# ProProject_J-Link_OB-RA4M2_20230930_V1_0.net
KiCad netlist of a schematic drawn in EasyEDA Pro
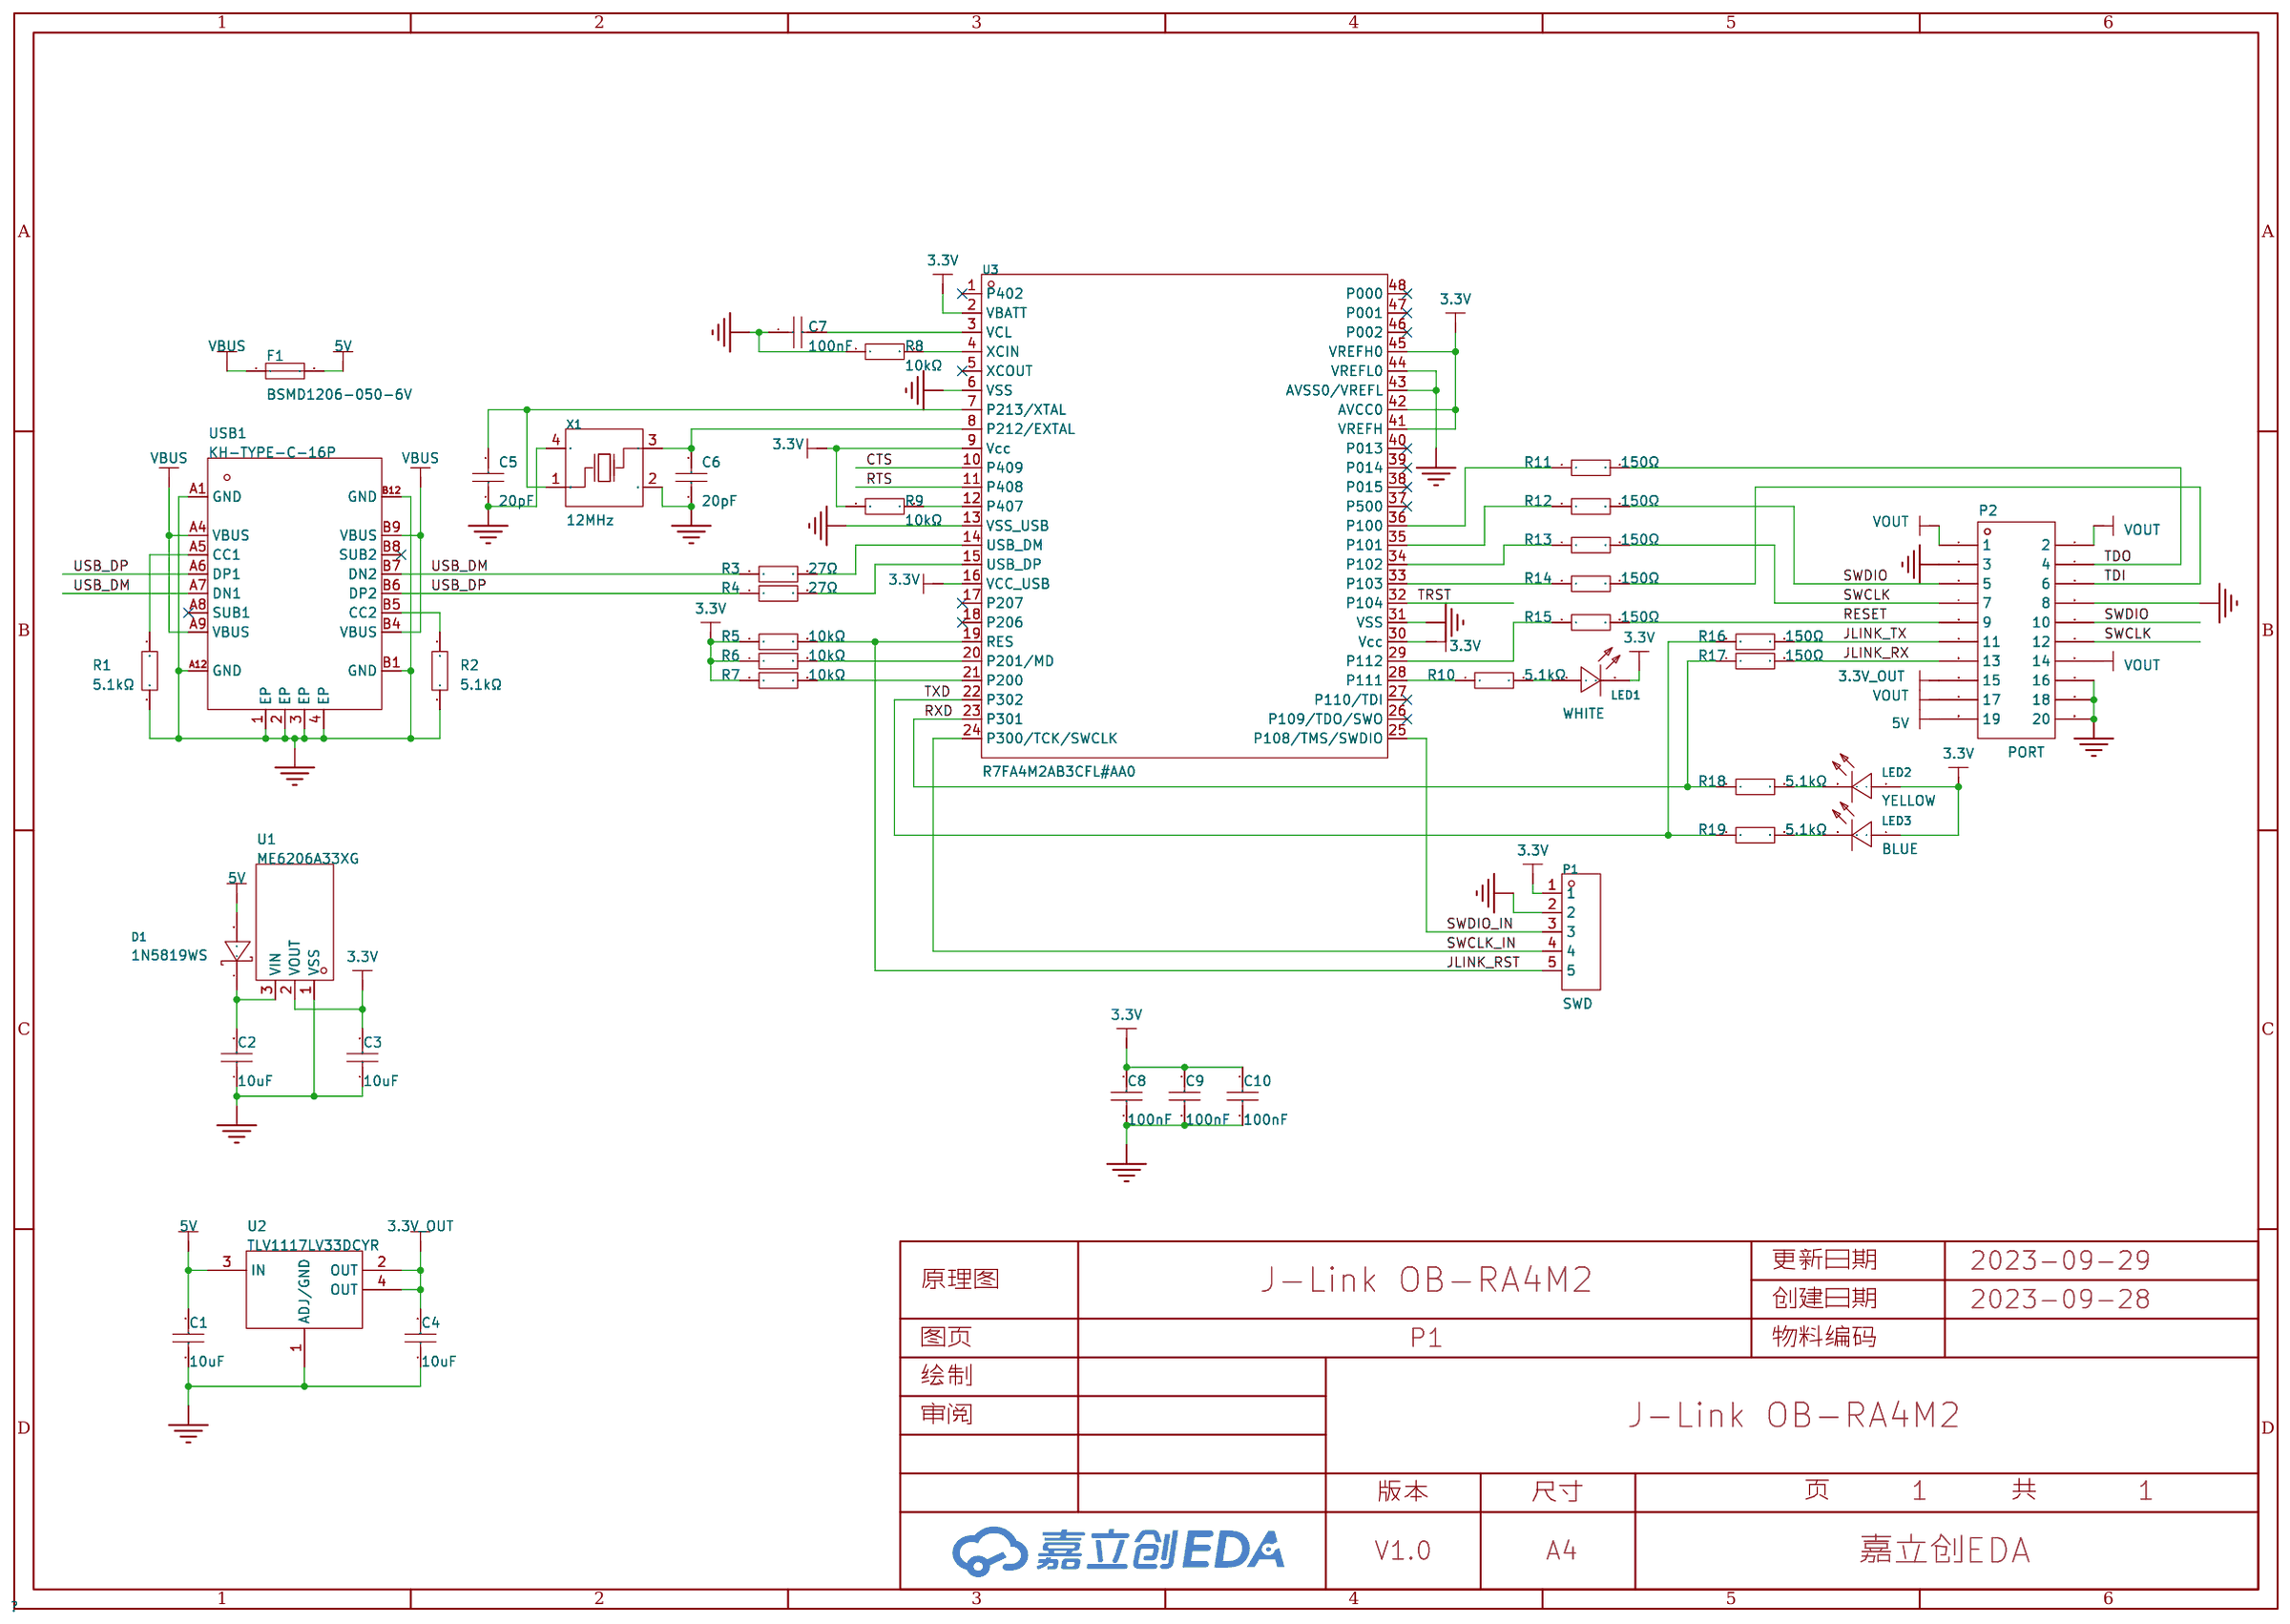
[diagram p0: schematic sheet]

(export (version "E")
  (design (tool "Eeschema 10.0.6"))
  (components
    (comp (ref "C1")
      (value "10uF")
      (footprint "easyedapro:C0805")
      (description "容值:10uF;精度:±10%;额定电压:25V;材质(温度系数):X5R;")
      (fields
        (field (name "Manufacturer Part") "CL21A106KAYNNNE")
        (field (name "Manufacturer") "SAMSUNG(三星)")
      )
      (libsource (lib "easyedapro") (part "CL21A106KAYNNNE"))
    )
    (comp (ref "C2")
      (value "10uF")
      (footprint "easyedapro:C0805")
      (description "容值:10uF;精度:±10%;额定电压:25V;材质(温度系数):X5R;")
      (fields
        (field (name "Manufacturer Part") "CL21A106KAYNNNE")
        (field (name "Manufacturer") "SAMSUNG(三星)")
      )
      (libsource (lib "easyedapro") (part "CL21A106KAYNNNE"))
    )
    (comp (ref "C3")
      (value "10uF")
      (footprint "easyedapro:C0805")
      (description "容值:10uF;精度:±10%;额定电压:25V;材质(温度系数):X5R;")
      (fields
        (field (name "Manufacturer Part") "CL21A106KAYNNNE")
        (field (name "Manufacturer") "SAMSUNG(三星)")
      )
      (libsource (lib "easyedapro") (part "CL21A106KAYNNNE"))
    )
    (comp (ref "C4")
      (value "10uF")
      (footprint "easyedapro:C0805")
      (description "容值:10uF;精度:±10%;额定电压:25V;材质(温度系数):X5R;")
      (fields
        (field (name "Manufacturer Part") "CL21A106KAYNNNE")
        (field (name "Manufacturer") "SAMSUNG(三星)")
      )
      (libsource (lib "easyedapro") (part "CL21A106KAYNNNE"))
    )
    (comp (ref "C5")
      (value "20pF")
      (footprint "easyedapro:C0805")
      (description "容值:20pF;精度:±5%;额定电压:50V;材质(温度系数):C0G;")
      (fields
        (field (name "Manufacturer Part") "CL10C200JB8NNNC")
        (field (name "Manufacturer") "SAMSUNG(三星)")
      )
      (libsource (lib "easyedapro") (part "CL21C200JBANNNC"))
    )
    (comp (ref "C6")
      (value "20pF")
      (footprint "easyedapro:C0805")
      (description "容值:20pF;精度:±5%;额定电压:50V;材质(温度系数):C0G;")
      (fields
        (field (name "Manufacturer Part") "CL10C200JB8NNNC")
        (field (name "Manufacturer") "SAMSUNG(三星)")
      )
      (libsource (lib "easyedapro") (part "CL21C200JBANNNC"))
    )
    (comp (ref "C7")
      (value "100nF")
      (footprint "easyedapro:C0805")
      (description "容值:100nF;精度:±10%;额定电压:50V;材质(温度系数):X7R;")
      (fields (field (name "Manufacturer Part") "0603B104K500NT") (field (name "Manufacturer") "FH(风华)"))
      (libsource (lib "easyedapro") (part "CC0805KRX7R9BB104"))
    )
    (comp (ref "C8")
      (value "100nF")
      (footprint "easyedapro:C0805")
      (description "容值:100nF;精度:±10%;额定电压:50V;材质(温度系数):X7R;")
      (fields (field (name "Manufacturer Part") "0603B104K500NT") (field (name "Manufacturer") "FH(风华)"))
      (libsource (lib "easyedapro") (part "CC0805KRX7R9BB104"))
    )
    (comp (ref "C9")
      (value "100nF")
      (footprint "easyedapro:C0805")
      (description "容值:100nF;精度:±10%;额定电压:50V;材质(温度系数):X7R;")
      (fields (field (name "Manufacturer Part") "0603B104K500NT") (field (name "Manufacturer") "FH(风华)"))
      (libsource (lib "easyedapro") (part "CC0805KRX7R9BB104"))
    )
    (comp (ref "C10")
      (value "100nF")
      (footprint "easyedapro:C0805")
      (description "容值:100nF;精度:±10%;额定电压:50V;材质(温度系数):X7R;")
      (fields (field (name "Manufacturer Part") "0603B104K500NT") (field (name "Manufacturer") "FH(风华)"))
      (libsource (lib "easyedapro") (part "CC0805KRX7R9BB104"))
    )
    (comp (ref "D1")
      (value "1N5819WS")
      (footprint "easyedapro:SOD-323_L1.8-W1.3-LS2.5-RD")
      (description "直流反向耐压(Vr):40V;平均整流电流(Io):1A;正向压降(Vf):600mV@1A;")
      (fields (field (name "Manufacturer") "Hottech(合科泰)"))
      (libsource (lib "easyedapro") (part "1N5819WS"))
    )
    (comp (ref "F1")
      (value "BSMD1206-050-6V")
      (footprint "easyedapro:F1206")
      (description "最大电压:6V;最大电流:100A;保持电流:500mA;跳闸电流:1A;")
      (fields (field (name "Manufacturer") "BHFUSE(佰宏)"))
      (libsource (lib "easyedapro") (part "BSMD1206-050-6V"))
    )
    (comp (ref "LED1")
      (value "WHITE")
      (footprint "easyedapro:LED0805-R-RD")
      (description "色温6000K左右")
      (fields (field (name "Manufacturer") "EVERLIGHT(亿光)"))
      (libsource (lib "easyedapro") (part "whiteLEDSMD"))
    )
    (comp (ref "LED2")
      (value "YELLOW")
      (footprint "easyedapro:LED0805-R-RD")
      (description "发光颜色:黄灯;二极管配置:-;透镜颜色:-;主波长:-;色温:-;功率:-;发光角度:-;安装方式:-;工作温度:-;")
      (fields (field (name "Manufacturer") "EVERLIGHT(亿光)"))
      (libsource (lib "easyedapro") (part "17-21SUYC/TR8"))
    )
    (comp (ref "LED3")
      (value "BLUE")
      (footprint "easyedapro:LED0805-R-RD")
      (fields (field (name "Manufacturer") "EVERLIGHT(亿光)"))
      (libsource (lib "easyedapro") (part "XL-0805QBC"))
    )
    (comp (ref "P1")
      (value "SWD")
      (footprint "easyedapro:HDR-TH_5P-P2.54-V-M")
      (fields (field (name "Manufacturer") "XFCN(兴飞)"))
      (libsource (lib "easyedapro") (part "PZ254V-11-05P"))
    )
    (comp (ref "P2")
      (value "PORT")
      (footprint "easyedapro:HDR-SMD_20P-P2.54")
      (fields (field (name "Manufacturer Part") "B-2100S20P-B110") (field (name "Manufacturer") "Ckmtw(灿科盟)"))
      (libsource (lib "easyedapro") (part "210S-2*10PL=11.6MM Gold-plated black"))
    )
    (comp (ref "R1")
      (value "5.1kΩ")
      (footprint "easyedapro:R0805")
      (description "电阻类型:厚膜电阻;阻值:5.1kΩ;精度:±1%;功率:125mW;")
      (fields
        (field (name "Manufacturer Part") "0603WAF5101T5E")
        (field (name "Manufacturer") "UNI-ROYAL(厚声)")
      )
      (libsource (lib "easyedapro") (part "0805W8F5101T5E"))
    )
    (comp (ref "R2")
      (value "5.1kΩ")
      (footprint "easyedapro:R0805")
      (description "电阻类型:厚膜电阻;阻值:5.1kΩ;精度:±1%;功率:125mW;")
      (fields
        (field (name "Manufacturer Part") "0603WAF5101T5E")
        (field (name "Manufacturer") "UNI-ROYAL(厚声)")
      )
      (libsource (lib "easyedapro") (part "0805W8F5101T5E"))
    )
    (comp (ref "R3")
      (value "27Ω")
      (footprint "easyedapro:R0805")
      (description "电阻类型:厚膜电阻;阻值:27Ω;精度:±1%;功率:125mW;")
      (fields
        (field (name "Manufacturer Part") "0603WAF270JT5E")
        (field (name "Manufacturer") "UNI-ROYAL(厚声)")
      )
      (libsource (lib "easyedapro") (part "RC0805FR-0727RL"))
    )
    (comp (ref "R4")
      (value "27Ω")
      (footprint "easyedapro:R0805")
      (description "电阻类型:厚膜电阻;阻值:27Ω;精度:±1%;功率:125mW;")
      (fields
        (field (name "Manufacturer Part") "0603WAF270JT5E")
        (field (name "Manufacturer") "UNI-ROYAL(厚声)")
      )
      (libsource (lib "easyedapro") (part "RC0805FR-0727RL"))
    )
    (comp (ref "R5")
      (value "10kΩ")
      (footprint "easyedapro:R0805")
      (description "阻值:10kΩ;精度:±1%;功率:125mW;温度系数:±100ppm/°C;最大工作电压:150V;工作温度范围:-55°C~+155°C;")
      (fields
        (field (name "Manufacturer Part") "0603WAF1002T5E")
        (field (name "Manufacturer") "UNI-ROYAL(厚声)")
      )
      (libsource (lib "easyedapro") (part "RC0805FR-0710KL"))
    )
    (comp (ref "R6")
      (value "10kΩ")
      (footprint "easyedapro:R0805")
      (description "阻值:10kΩ;精度:±1%;功率:125mW;温度系数:±100ppm/°C;最大工作电压:150V;工作温度范围:-55°C~+155°C;")
      (fields
        (field (name "Manufacturer Part") "0603WAF1002T5E")
        (field (name "Manufacturer") "UNI-ROYAL(厚声)")
      )
      (libsource (lib "easyedapro") (part "RC0805FR-0710KL"))
    )
    (comp (ref "R7")
      (value "10kΩ")
      (footprint "easyedapro:R0805")
      (description "阻值:10kΩ;精度:±1%;功率:125mW;温度系数:±100ppm/°C;最大工作电压:150V;工作温度范围:-55°C~+155°C;")
      (fields
        (field (name "Manufacturer Part") "0603WAF1002T5E")
        (field (name "Manufacturer") "UNI-ROYAL(厚声)")
      )
      (libsource (lib "easyedapro") (part "RC0805FR-0710KL"))
    )
    (comp (ref "R8")
      (value "10kΩ")
      (footprint "easyedapro:R0805")
      (description "阻值:10kΩ;精度:±1%;功率:125mW;温度系数:±100ppm/°C;最大工作电压:150V;工作温度范围:-55°C~+155°C;")
      (fields
        (field (name "Manufacturer Part") "0603WAF1002T5E")
        (field (name "Manufacturer") "UNI-ROYAL(厚声)")
      )
      (libsource (lib "easyedapro") (part "RC0805FR-0710KL"))
    )
    (comp (ref "R9")
      (value "10kΩ")
      (footprint "easyedapro:R0805")
      (description "阻值:10kΩ;精度:±1%;功率:125mW;温度系数:±100ppm/°C;最大工作电压:150V;工作温度范围:-55°C~+155°C;")
      (fields
        (field (name "Manufacturer Part") "0603WAF1002T5E")
        (field (name "Manufacturer") "UNI-ROYAL(厚声)")
      )
      (libsource (lib "easyedapro") (part "RC0805FR-0710KL"))
    )
    (comp (ref "R10")
      (value "5.1kΩ")
      (footprint "easyedapro:R0805")
      (description "电阻类型:厚膜电阻;阻值:5.1kΩ;精度:±1%;功率:125mW;")
      (fields
        (field (name "Manufacturer Part") "0603WAF5101T5E")
        (field (name "Manufacturer") "UNI-ROYAL(厚声)")
      )
      (libsource (lib "easyedapro") (part "0805W8F5101T5E"))
    )
    (comp (ref "R11")
      (value "150Ω")
      (footprint "easyedapro:R0805")
      (description "电阻类型:厚膜电阻;阻值:150Ω;精度:±1%;功率:125mW;")
      (fields
        (field (name "Manufacturer Part") "0603WAF1500T5E")
        (field (name "Manufacturer") "UNI-ROYAL(厚声)")
      )
      (libsource (lib "easyedapro") (part "0805W8F1500T5E"))
    )
    (comp (ref "R12")
      (value "150Ω")
      (footprint "easyedapro:R0805")
      (description "电阻类型:厚膜电阻;阻值:150Ω;精度:±1%;功率:125mW;")
      (fields
        (field (name "Manufacturer Part") "0603WAF1500T5E")
        (field (name "Manufacturer") "UNI-ROYAL(厚声)")
      )
      (libsource (lib "easyedapro") (part "0805W8F1500T5E"))
    )
    (comp (ref "R13")
      (value "150Ω")
      (footprint "easyedapro:R0805")
      (description "电阻类型:厚膜电阻;阻值:150Ω;精度:±1%;功率:125mW;")
      (fields
        (field (name "Manufacturer Part") "0603WAF1500T5E")
        (field (name "Manufacturer") "UNI-ROYAL(厚声)")
      )
      (libsource (lib "easyedapro") (part "0805W8F1500T5E"))
    )
    (comp (ref "R14")
      (value "150Ω")
      (footprint "easyedapro:R0805")
      (description "电阻类型:厚膜电阻;阻值:150Ω;精度:±1%;功率:125mW;")
      (fields
        (field (name "Manufacturer Part") "0603WAF1500T5E")
        (field (name "Manufacturer") "UNI-ROYAL(厚声)")
      )
      (libsource (lib "easyedapro") (part "0805W8F1500T5E"))
    )
    (comp (ref "R15")
      (value "150Ω")
      (footprint "easyedapro:R0805")
      (description "电阻类型:厚膜电阻;阻值:150Ω;精度:±1%;功率:125mW;")
      (fields
        (field (name "Manufacturer Part") "0603WAF1500T5E")
        (field (name "Manufacturer") "UNI-ROYAL(厚声)")
      )
      (libsource (lib "easyedapro") (part "0805W8F1500T5E"))
    )
    (comp (ref "R16")
      (value "150Ω")
      (footprint "easyedapro:R0805")
      (description "电阻类型:厚膜电阻;阻值:150Ω;精度:±1%;功率:125mW;")
      (fields
        (field (name "Manufacturer Part") "0603WAF1500T5E")
        (field (name "Manufacturer") "UNI-ROYAL(厚声)")
      )
      (libsource (lib "easyedapro") (part "0805W8F1500T5E"))
    )
    (comp (ref "R17")
      (value "150Ω")
      (footprint "easyedapro:R0805")
      (description "电阻类型:厚膜电阻;阻值:150Ω;精度:±1%;功率:125mW;")
      (fields
        (field (name "Manufacturer Part") "0603WAF1500T5E")
        (field (name "Manufacturer") "UNI-ROYAL(厚声)")
      )
      (libsource (lib "easyedapro") (part "0805W8F1500T5E"))
    )
    (comp (ref "R18")
      (value "5.1kΩ")
      (footprint "easyedapro:R0805")
      (description "电阻类型:厚膜电阻;阻值:5.1kΩ;精度:±1%;功率:125mW;")
      (fields
        (field (name "Manufacturer Part") "0603WAF5101T5E")
        (field (name "Manufacturer") "UNI-ROYAL(厚声)")
      )
      (libsource (lib "easyedapro") (part "0805W8F5101T5E"))
    )
    (comp (ref "R19")
      (value "5.1kΩ")
      (footprint "easyedapro:R0805")
      (description "电阻类型:厚膜电阻;阻值:5.1kΩ;精度:±1%;功率:125mW;")
      (fields
        (field (name "Manufacturer Part") "0603WAF5101T5E")
        (field (name "Manufacturer") "UNI-ROYAL(厚声)")
      )
      (libsource (lib "easyedapro") (part "0805W8F5101T5E"))
    )
    (comp (ref "U1")
      (value "ME6206A33XG")
      (footprint "easyedapro:SOT-23-3_L2.9-W1.6-P1.90-LS2.8-BR")
      (description "最大输入电压:6V;压降(max):400mV @ 200mA;输出电压(可调):-;静态电流(Iq):-;输出类型:固定;输出电压(固定):3.3V;")
      (fields (field (name "Manufacturer") "MICRONE(南京微盟)"))
      (libsource (lib "easyedapro") (part "ME6206A33XG"))
    )
    (comp (ref "U2")
      (value "TLV1117LV33DCYR")
      (footprint "easyedapro:SOT-223_L6.7-W3.5-P2.30-BR")
      (description "输出类型:固定;输出极性:正;最大输入电压:5.5V;输出电压:3.3V;输出电流:1A;电源纹波抑制比(PSRR):75dB@(120Hz);")
      (fields (field (name "Manufacturer") "TI(德州仪器)"))
      (libsource (lib "easyedapro") (part "TLV1117LV33DCYR"))
    )
    (comp (ref "U3")
      (value "R7FA4M2AB3CFL#AA0")
      (footprint "easyedapro:LQFP-48_L7.0-W7.0-P0.50-LS9.0-BL")
      (description "CPU内核:ARM-M系列;CPU最大主频:100MHz;工作电压范围:2.7V~3.6V;程序存储容量:254KB;GPIO端口数量:30;")
      (fields (field (name "Manufacturer") "RENESAS(瑞萨)/IDT"))
      (libsource (lib "easyedapro") (part "R7FA4M2AB3CFL#AA0"))
    )
    (comp (ref "USB1")
      (value "KH-TYPE-C-16P")
      (footprint "easyedapro:USB-C-SMD_KH-TYPE-C-16P")
      (description "连接器类型:Type-C;标准:-;公母:母座;触点数量:16;端口数量:1;安装方式:卧贴;额定电流 - 电源:3A;工作温度范围:-40~+85;")
      (fields (field (name "Manufacturer") "kinghelm(金航标)"))
      (libsource (lib "easyedapro") (part "KH-TYPE-C-16P"))
    )
    (comp (ref "X1")
      (value "12MHz")
      (footprint "easyedapro:OSC-SMD_4P-L3.2-W2.5-BL")
      (description "频率:12MHz;频率公差:±10ppm;负载电容:20pF;")
      (fields (field (name "Manufacturer Part") "X322512MSB4SI") (field (name "Manufacturer") "YXC(扬兴晶振)"))
      (libsource (lib "easyedapro") (part "X322512MSB4SI"))
    )
  )
  (nets
    (net (code "1") (name "/CTS") (class "Default")
      (node (ref "U3") (pin "10") (pinfunction "P409_10") (pintype "input"))
    )
    (net (code "2") (name "/JLINK_RST") (class "Default")
      (node (ref "P1") (pin "5") (pinfunction "5_5") (pintype "input"))
      (node (ref "R5") (pin "2") (pinfunction "2_2") (pintype "input"))
      (node (ref "U3") (pin "19") (pinfunction "RES_19") (pintype "input"))
    )
    (net (code "3") (name "/JLINK_RX") (class "Default")
      (node (ref "P2") (pin "13") (pinfunction "13_13") (pintype "input"))
      (node (ref "R17") (pin "2") (pinfunction "2_2") (pintype "input"))
    )
    (net (code "4") (name "/JLINK_TX") (class "Default")
      (node (ref "P2") (pin "11") (pinfunction "11_11") (pintype "input"))
      (node (ref "R16") (pin "2") (pinfunction "2_2") (pintype "input"))
    )
    (net (code "5") (name "/RESET") (class "Default")
      (node (ref "P2") (pin "9") (pinfunction "9_9") (pintype "input"))
      (node (ref "R15") (pin "2") (pinfunction "2_2") (pintype "input"))
    )
    (net (code "6") (name "/RTS") (class "Default")
      (node (ref "U3") (pin "11") (pinfunction "P408_11") (pintype "input"))
    )
    (net (code "7") (name "/RXD") (class "Default")
      (node (ref "R17") (pin "1") (pinfunction "1_1") (pintype "input"))
      (node (ref "R18") (pin "1") (pinfunction "1_1") (pintype "input"))
      (node (ref "U3") (pin "23") (pinfunction "P301_23") (pintype "input"))
    )
    (net (code "8") (name "/SWCLK") (class "Default")
      (node (ref "P2") (pin "12") (pinfunction "12_12") (pintype "input"))
      (node (ref "P2") (pin "7") (pinfunction "7_7") (pintype "input"))
      (node (ref "R13") (pin "2") (pinfunction "2_2") (pintype "input"))
    )
    (net (code "9") (name "/SWCLK_IN") (class "Default")
      (node (ref "P1") (pin "4") (pinfunction "4_4") (pintype "input"))
      (node (ref "U3") (pin "24") (pinfunction "P300/TCK/SWCLK_24") (pintype "input"))
    )
    (net (code "10") (name "/SWDIO") (class "Default")
      (node (ref "P2") (pin "10") (pinfunction "10_10") (pintype "input"))
      (node (ref "P2") (pin "5") (pinfunction "5_5") (pintype "input"))
      (node (ref "R12") (pin "2") (pinfunction "2_2") (pintype "input"))
    )
    (net (code "11") (name "/SWDIO_IN") (class "Default")
      (node (ref "P1") (pin "3") (pinfunction "3_3") (pintype "input"))
      (node (ref "U3") (pin "25") (pinfunction "P108/TMS/SWDIO_25") (pintype "input"))
    )
    (net (code "12") (name "/TDI") (class "Default")
      (node (ref "P2") (pin "6") (pinfunction "6_6") (pintype "input"))
      (node (ref "R14") (pin "2") (pinfunction "2_2") (pintype "input"))
    )
    (net (code "13") (name "/TDO") (class "Default")
      (node (ref "P2") (pin "4") (pinfunction "4_4") (pintype "input"))
      (node (ref "R11") (pin "2") (pinfunction "2_2") (pintype "input"))
    )
    (net (code "14") (name "/TRST") (class "Default")
      (node (ref "U3") (pin "32") (pinfunction "P104_32") (pintype "input"))
    )
    (net (code "15") (name "/TXD") (class "Default")
      (node (ref "R16") (pin "1") (pinfunction "1_1") (pintype "input"))
      (node (ref "R19") (pin "1") (pinfunction "1_1") (pintype "input"))
      (node (ref "U3") (pin "22") (pinfunction "P302_22") (pintype "input"))
    )
    (net (code "16") (name "/USB_DM") (class "Default")
      (node (ref "R3") (pin "1") (pinfunction "1_1") (pintype "input"))
      (node (ref "USB1") (pin "A7") (pinfunction "DN1_A7") (pintype "input"))
      (node (ref "USB1") (pin "B7") (pinfunction "DN2_B7") (pintype "input"))
    )
    (net (code "17") (name "/USB_DP") (class "Default")
      (node (ref "R4") (pin "1") (pinfunction "1_1") (pintype "input"))
      (node (ref "USB1") (pin "A6") (pinfunction "DP1_A6") (pintype "input"))
      (node (ref "USB1") (pin "B6") (pinfunction "DP2_B6") (pintype "input"))
    )
    (net (code "18") (name "3.3V") (class "Default")
      (node (ref "C10") (pin "2") (pinfunction "2_2") (pintype "input"))
      (node (ref "C3") (pin "2") (pinfunction "2_2") (pintype "input"))
      (node (ref "C8") (pin "2") (pinfunction "2_2") (pintype "input"))
      (node (ref "C9") (pin "2") (pinfunction "2_2") (pintype "input"))
      (node (ref "LED1") (pin "2") (pinfunction "K_2") (pintype "input"))
      (node (ref "LED2") (pin "1") (pinfunction "+_1") (pintype "input"))
      (node (ref "LED3") (pin "1") (pinfunction "A_1") (pintype "input"))
      (node (ref "P1") (pin "1") (pinfunction "1_1") (pintype "input"))
      (node (ref "R5") (pin "1") (pinfunction "1_1") (pintype "input"))
      (node (ref "R6") (pin "1") (pinfunction "1_1") (pintype "input"))
      (node (ref "R7") (pin "1") (pinfunction "1_1") (pintype "input"))
      (node (ref "R9") (pin "1") (pinfunction "1_1") (pintype "input"))
      (node (ref "U1") (pin "2") (pinfunction "VOUT_2") (pintype "input"))
      (node (ref "U3") (pin "16") (pinfunction "VCC_USB_16") (pintype "input"))
      (node (ref "U3") (pin "2") (pinfunction "VBATT_2") (pintype "input"))
      (node (ref "U3") (pin "30") (pinfunction "Vcc_30") (pintype "input"))
      (node (ref "U3") (pin "41") (pinfunction "VREFH_41") (pintype "input"))
      (node (ref "U3") (pin "42") (pinfunction "AVCC0_42") (pintype "input"))
      (node (ref "U3") (pin "45") (pinfunction "VREFH0_45") (pintype "input"))
      (node (ref "U3") (pin "9") (pinfunction "Vcc_9") (pintype "input"))
    )
    (net (code "19") (name "3.3V_OUT") (class "Default")
      (node (ref "C4") (pin "2") (pinfunction "2_2") (pintype "input"))
      (node (ref "P2") (pin "15") (pinfunction "15_15") (pintype "input"))
      (node (ref "U2") (pin "2") (pinfunction "OUT_2") (pintype "input"))
      (node (ref "U2") (pin "4") (pinfunction "OUT_4") (pintype "input"))
    )
    (net (code "20") (name "5V") (class "Default")
      (node (ref "C1") (pin "2") (pinfunction "2_2") (pintype "input"))
      (node (ref "D1") (pin "2") (pinfunction "A_2") (pintype "input"))
      (node (ref "F1") (pin "2") (pinfunction "2_2") (pintype "input"))
      (node (ref "P2") (pin "19") (pinfunction "19_19") (pintype "input"))
      (node (ref "U2") (pin "3") (pinfunction "IN_3") (pintype "input"))
    )
    (net (code "21") (name "GND") (class "Default")
      (node (ref "C1") (pin "1") (pinfunction "1_1") (pintype "input"))
      (node (ref "C10") (pin "1") (pinfunction "1_1") (pintype "input"))
      (node (ref "C2") (pin "1") (pinfunction "1_1") (pintype "input"))
      (node (ref "C3") (pin "1") (pinfunction "1_1") (pintype "input"))
      (node (ref "C4") (pin "1") (pinfunction "1_1") (pintype "input"))
      (node (ref "C5") (pin "1") (pinfunction "1_1") (pintype "input"))
      (node (ref "C6") (pin "1") (pinfunction "1_1") (pintype "input"))
      (node (ref "C7") (pin "1") (pinfunction "1_1") (pintype "input"))
      (node (ref "C8") (pin "1") (pinfunction "1_1") (pintype "input"))
      (node (ref "C9") (pin "1") (pinfunction "1_1") (pintype "input"))
      (node (ref "P1") (pin "2") (pinfunction "2_2") (pintype "input"))
      (node (ref "P2") (pin "16") (pinfunction "16_16") (pintype "input"))
      (node (ref "P2") (pin "18") (pinfunction "18_18") (pintype "input"))
      (node (ref "P2") (pin "20") (pinfunction "20_20") (pintype "input"))
      (node (ref "P2") (pin "3") (pinfunction "3_3") (pintype "input"))
      (node (ref "P2") (pin "8") (pinfunction "8_8") (pintype "input"))
      (node (ref "R1") (pin "1") (pinfunction "1_1") (pintype "input"))
      (node (ref "R2") (pin "1") (pinfunction "1_1") (pintype "input"))
      (node (ref "R8") (pin "1") (pinfunction "1_1") (pintype "input"))
      (node (ref "U1") (pin "1") (pinfunction "VSS_1") (pintype "input"))
      (node (ref "U2") (pin "1") (pinfunction "ADJ/GND_1") (pintype "input"))
      (node (ref "U3") (pin "13") (pinfunction "VSS_USB_13") (pintype "input"))
      (node (ref "U3") (pin "31") (pinfunction "VSS_31") (pintype "input"))
      (node (ref "U3") (pin "43") (pinfunction "AVSS0/VREFL_43") (pintype "input"))
      (node (ref "U3") (pin "44") (pinfunction "VREFL0_44") (pintype "input"))
      (node (ref "U3") (pin "6") (pinfunction "VSS_6") (pintype "input"))
      (node (ref "USB1") (pin "1") (pinfunction "EP_1") (pintype "input"))
      (node (ref "USB1") (pin "2") (pinfunction "EP_2") (pintype "input"))
      (node (ref "USB1") (pin "3") (pinfunction "EP_3") (pintype "input"))
      (node (ref "USB1") (pin "4") (pinfunction "EP_4") (pintype "input"))
      (node (ref "USB1") (pin "A1") (pinfunction "GND_A1") (pintype "input"))
      (node (ref "USB1") (pin "A12") (pinfunction "GND_A12") (pintype "input"))
      (node (ref "USB1") (pin "B1") (pinfunction "GND_B1") (pintype "input"))
      (node (ref "USB1") (pin "B12") (pinfunction "GND_B12") (pintype "input"))
      (node (ref "X1") (pin "2") (pinfunction "GND_2") (pintype "input"))
      (node (ref "X1") (pin "4") (pinfunction "GND_4") (pintype "input"))
    )
    (net (code "22") (name "Net-(D1-K)") (class "Default")
      (node (ref "C2") (pin "2") (pinfunction "2_2") (pintype "input"))
      (node (ref "D1") (pin "1") (pinfunction "K_1") (pintype "input"))
      (node (ref "U1") (pin "3") (pinfunction "VIN_3") (pintype "input"))
    )
    (net (code "23") (name "Net-(LED1-A)") (class "Default")
      (node (ref "LED1") (pin "1") (pinfunction "A_1") (pintype "input"))
      (node (ref "R10") (pin "2") (pinfunction "2_2") (pintype "input"))
    )
    (net (code "24") (name "Net-(LED2--)") (class "Default")
      (node (ref "LED2") (pin "2") (pinfunction "-_2") (pintype "input"))
      (node (ref "R18") (pin "2") (pinfunction "2_2") (pintype "input"))
    )
    (net (code "25") (name "Net-(LED3-K)") (class "Default")
      (node (ref "LED3") (pin "2") (pinfunction "K_2") (pintype "input"))
      (node (ref "R19") (pin "2") (pinfunction "2_2") (pintype "input"))
    )
    (net (code "26") (name "Net-(U3-P100)") (class "Default")
      (node (ref "R11") (pin "1") (pinfunction "1_1") (pintype "input"))
      (node (ref "U3") (pin "36") (pinfunction "P100_36") (pintype "input"))
    )
    (net (code "27") (name "Net-(U3-P101)") (class "Default")
      (node (ref "R12") (pin "1") (pinfunction "1_1") (pintype "input"))
      (node (ref "U3") (pin "35") (pinfunction "P101_35") (pintype "input"))
    )
    (net (code "28") (name "Net-(U3-P102)") (class "Default")
      (node (ref "R13") (pin "1") (pinfunction "1_1") (pintype "input"))
      (node (ref "U3") (pin "34") (pinfunction "P102_34") (pintype "input"))
    )
    (net (code "29") (name "Net-(U3-P103)") (class "Default")
      (node (ref "R14") (pin "1") (pinfunction "1_1") (pintype "input"))
      (node (ref "U3") (pin "33") (pinfunction "P103_33") (pintype "input"))
    )
    (net (code "30") (name "Net-(U3-P111)") (class "Default")
      (node (ref "R10") (pin "1") (pinfunction "1_1") (pintype "input"))
      (node (ref "U3") (pin "28") (pinfunction "P111_28") (pintype "input"))
    )
    (net (code "31") (name "Net-(U3-P112)") (class "Default")
      (node (ref "R15") (pin "1") (pinfunction "1_1") (pintype "input"))
      (node (ref "U3") (pin "29") (pinfunction "P112_29") (pintype "input"))
    )
    (net (code "32") (name "Net-(U3-P200)") (class "Default")
      (node (ref "R7") (pin "2") (pinfunction "2_2") (pintype "input"))
      (node (ref "U3") (pin "21") (pinfunction "P200_21") (pintype "input"))
    )
    (net (code "33") (name "Net-(U3-P201{slash}MD)") (class "Default")
      (node (ref "R6") (pin "2") (pinfunction "2_2") (pintype "input"))
      (node (ref "U3") (pin "20") (pinfunction "P201/MD_20") (pintype "input"))
    )
    (net (code "34") (name "Net-(U3-P212{slash}EXTAL)") (class "Default")
      (node (ref "C6") (pin "2") (pinfunction "2_2") (pintype "input"))
      (node (ref "U3") (pin "8") (pinfunction "P212/EXTAL_8") (pintype "input"))
      (node (ref "X1") (pin "3") (pinfunction "OSC2_3") (pintype "input"))
    )
    (net (code "35") (name "Net-(U3-P213{slash}XTAL)") (class "Default")
      (node (ref "C5") (pin "2") (pinfunction "2_2") (pintype "input"))
      (node (ref "U3") (pin "7") (pinfunction "P213/XTAL_7") (pintype "input"))
      (node (ref "X1") (pin "1") (pinfunction "OSC1_1") (pintype "input"))
    )
    (net (code "36") (name "Net-(U3-P407)") (class "Default")
      (node (ref "R9") (pin "2") (pinfunction "2_2") (pintype "input"))
      (node (ref "U3") (pin "12") (pinfunction "P407_12") (pintype "input"))
    )
    (net (code "37") (name "Net-(U3-USB_DM)") (class "Default")
      (node (ref "R3") (pin "2") (pinfunction "2_2") (pintype "input"))
      (node (ref "U3") (pin "14") (pinfunction "USB_DM_14") (pintype "input"))
    )
    (net (code "38") (name "Net-(U3-USB_DP)") (class "Default")
      (node (ref "R4") (pin "2") (pinfunction "2_2") (pintype "input"))
      (node (ref "U3") (pin "15") (pinfunction "USB_DP_15") (pintype "input"))
    )
    (net (code "39") (name "Net-(U3-VCL)") (class "Default")
      (node (ref "C7") (pin "2") (pinfunction "2_2") (pintype "input"))
      (node (ref "U3") (pin "3") (pinfunction "VCL_3") (pintype "input"))
    )
    (net (code "40") (name "Net-(U3-XCIN)") (class "Default")
      (node (ref "R8") (pin "2") (pinfunction "2_2") (pintype "input"))
      (node (ref "U3") (pin "4") (pinfunction "XCIN_4") (pintype "input"))
    )
    (net (code "41") (name "Net-(USB1-CC1)") (class "Default")
      (node (ref "R1") (pin "2") (pinfunction "2_2") (pintype "input"))
      (node (ref "USB1") (pin "A5") (pinfunction "CC1_A5") (pintype "input"))
    )
    (net (code "42") (name "Net-(USB1-CC2)") (class "Default")
      (node (ref "R2") (pin "2") (pinfunction "2_2") (pintype "input"))
      (node (ref "USB1") (pin "B5") (pinfunction "CC2_B5") (pintype "input"))
    )
    (net (code "43") (name "VBUS") (class "Default")
      (node (ref "F1") (pin "1") (pinfunction "1_1") (pintype "input"))
      (node (ref "USB1") (pin "A4") (pinfunction "VBUS_A4") (pintype "input"))
      (node (ref "USB1") (pin "A9") (pinfunction "VBUS_A9") (pintype "input"))
      (node (ref "USB1") (pin "B4") (pinfunction "VBUS_B4") (pintype "input"))
      (node (ref "USB1") (pin "B9") (pinfunction "VBUS_B9") (pintype "input"))
    )
    (net (code "44") (name "VOUT") (class "Default")
      (node (ref "P2") (pin "1") (pinfunction "1_1") (pintype "input"))
      (node (ref "P2") (pin "14") (pinfunction "14_14") (pintype "input"))
      (node (ref "P2") (pin "17") (pinfunction "17_17") (pintype "input"))
      (node (ref "P2") (pin "2") (pinfunction "2_2") (pintype "input"))
    )
    (net (code "45") (name "unconnected-(U3-P000-Pad48)") (class "Default")
      (node (ref "U3") (pin "48") (pinfunction "P000_48") (pintype "input+no_connect"))
    )
    (net (code "46") (name "unconnected-(U3-P001-Pad47)") (class "Default")
      (node (ref "U3") (pin "47") (pinfunction "P001_47") (pintype "input+no_connect"))
    )
    (net (code "47") (name "unconnected-(U3-P002-Pad46)") (class "Default")
      (node (ref "U3") (pin "46") (pinfunction "P002_46") (pintype "input+no_connect"))
    )
    (net (code "48") (name "unconnected-(U3-P013-Pad40)") (class "Default")
      (node (ref "U3") (pin "40") (pinfunction "P013_40") (pintype "input+no_connect"))
    )
    (net (code "49") (name "unconnected-(U3-P014-Pad39)") (class "Default")
      (node (ref "U3") (pin "39") (pinfunction "P014_39") (pintype "input+no_connect"))
    )
    (net (code "50") (name "unconnected-(U3-P015-Pad38)") (class "Default")
      (node (ref "U3") (pin "38") (pinfunction "P015_38") (pintype "input+no_connect"))
    )
    (net (code "51") (name "unconnected-(U3-P109{slash}TDO{slash}SWO-Pad26)") (class "Default")
      (node (ref "U3") (pin "26") (pinfunction "P109/TDO/SWO_26") (pintype "input+no_connect"))
    )
    (net (code "52") (name "unconnected-(U3-P110{slash}TDI-Pad27)") (class "Default")
      (node (ref "U3") (pin "27") (pinfunction "P110/TDI_27") (pintype "input+no_connect"))
    )
    (net (code "53") (name "unconnected-(U3-P206-Pad18)") (class "Default")
      (node (ref "U3") (pin "18") (pinfunction "P206_18") (pintype "input+no_connect"))
    )
    (net (code "54") (name "unconnected-(U3-P207-Pad17)") (class "Default")
      (node (ref "U3") (pin "17") (pinfunction "P207_17") (pintype "input+no_connect"))
    )
    (net (code "55") (name "unconnected-(U3-P402-Pad1)") (class "Default")
      (node (ref "U3") (pin "1") (pinfunction "P402_1") (pintype "input+no_connect"))
    )
    (net (code "56") (name "unconnected-(U3-P500-Pad37)") (class "Default")
      (node (ref "U3") (pin "37") (pinfunction "P500_37") (pintype "input+no_connect"))
    )
    (net (code "57") (name "unconnected-(U3-XCOUT-Pad5)") (class "Default")
      (node (ref "U3") (pin "5") (pinfunction "XCOUT_5") (pintype "input+no_connect"))
    )
    (net (code "58") (name "unconnected-(USB1-SUB1-PadA8)") (class "Default")
      (node (ref "USB1") (pin "A8") (pinfunction "SUB1_A8") (pintype "input+no_connect"))
    )
    (net (code "59") (name "unconnected-(USB1-SUB2-PadB8)") (class "Default")
      (node (ref "USB1") (pin "B8") (pinfunction "SUB2_B8") (pintype "input+no_connect"))
    )
  )
)
